# Machine_interlock_controller.net
KiCad netlist of a schematic drawn in Altium Designer
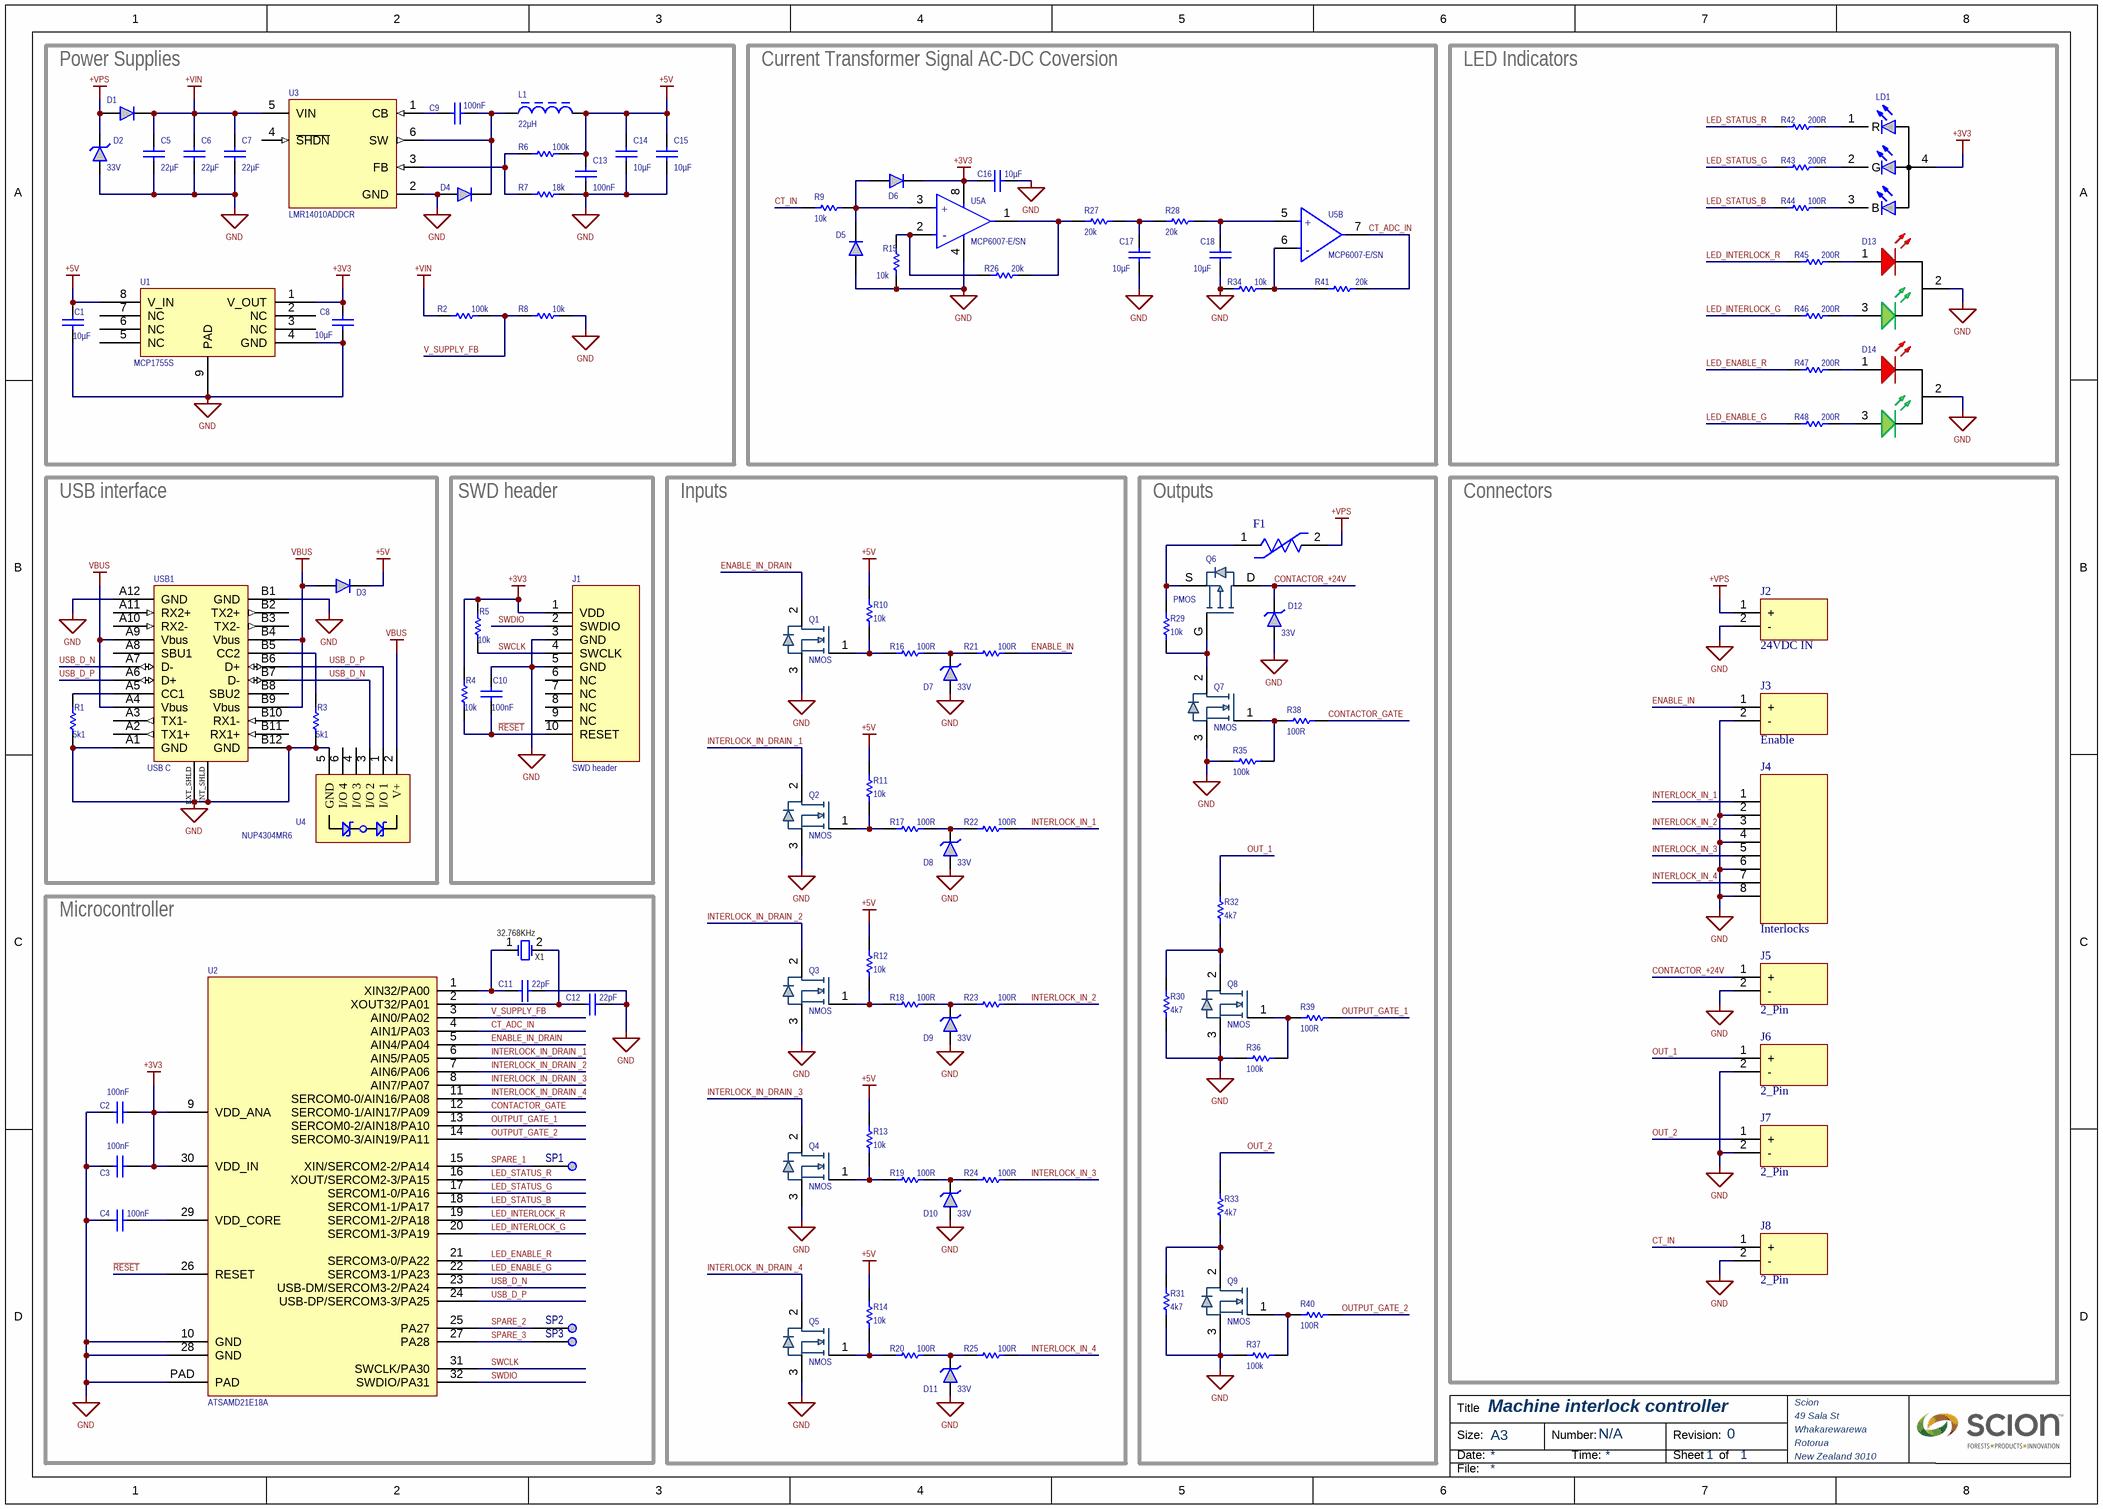
[diagram p0: Machine interlock controller.SchDoc]

(export (version "E")
  (design (tool "Eeschema 10.0.6"))
  (components
    (comp (ref "C1")
      (value "10µF")
      (footprint "0603_CAP")
      (description "SMD Capacitor")
      (fields (field (name "Comment") "Capacitor"))
      (libsource (lib "Scion Research") (part "CMP-019-00005-2"))
    )
    (comp (ref "C2")
      (value "100nF")
      (footprint "0603_CAP")
      (description "SMD Capacitor")
      (fields (field (name "Comment") "Capacitor"))
      (libsource (lib "Scion Research") (part "CMP-019-00005-2"))
    )
    (comp (ref "C3")
      (value "100nF")
      (footprint "0603_CAP")
      (description "SMD Capacitor")
      (fields (field (name "Comment") "Capacitor"))
      (libsource (lib "Scion Research") (part "CMP-019-00005-2"))
    )
    (comp (ref "C4")
      (value "100nF")
      (footprint "0603_CAP")
      (description "SMD Capacitor")
      (fields (field (name "Comment") "Capacitor"))
      (libsource (lib "Scion Research") (part "CMP-019-00005-2"))
    )
    (comp (ref "C5")
      (value "22µF")
      (footprint "0805_CAP")
      (description "SMD Capacitor")
      (fields (field (name "Comment") "Capacitor"))
      (libsource (lib "Scion Research") (part "CMP-019-00005-2"))
    )
    (comp (ref "C6")
      (value "22µF")
      (footprint "0805_CAP")
      (description "SMD Capacitor")
      (fields (field (name "Comment") "Capacitor"))
      (libsource (lib "Scion Research") (part "CMP-019-00005-2"))
    )
    (comp (ref "C7")
      (value "22µF")
      (footprint "0805_CAP")
      (description "SMD Capacitor")
      (fields (field (name "Comment") "Capacitor"))
      (libsource (lib "Scion Research") (part "CMP-019-00005-2"))
    )
    (comp (ref "C8")
      (value "10µF")
      (footprint "0603_CAP")
      (description "SMD Capacitor")
      (fields (field (name "Comment") "Capacitor"))
      (libsource (lib "Scion Research") (part "CMP-019-00005-2"))
    )
    (comp (ref "C9")
      (value "100nF")
      (footprint "0603_CAP")
      (description "SMD Capacitor")
      (fields (field (name "Comment") "Capacitor"))
      (libsource (lib "Scion Research") (part "CMP-019-00005-2"))
    )
    (comp (ref "C10")
      (value "100nF")
      (footprint "0603_CAP")
      (description "SMD Capacitor")
      (fields (field (name "Comment") "Capacitor"))
      (libsource (lib "Scion Research") (part "CMP-019-00005-2"))
    )
    (comp (ref "C11")
      (value "22pF")
      (footprint "0603_CAP")
      (description "SMD Capacitor")
      (fields (field (name "Comment") "Capacitor"))
      (libsource (lib "Scion Research") (part "CMP-019-00005-2"))
    )
    (comp (ref "C12")
      (value "22pF")
      (footprint "0603_CAP")
      (description "SMD Capacitor")
      (fields (field (name "Comment") "Capacitor"))
      (libsource (lib "Scion Research") (part "CMP-019-00005-2"))
    )
    (comp (ref "C13")
      (value "100nF")
      (footprint "0603_CAP")
      (description "SMD Capacitor")
      (fields (field (name "Comment") "Capacitor"))
      (libsource (lib "Scion Research") (part "CMP-019-00005-2"))
    )
    (comp (ref "C14")
      (value "10µF")
      (footprint "0603_CAP")
      (description "SMD Capacitor")
      (fields (field (name "Comment") "Capacitor"))
      (libsource (lib "Scion Research") (part "CMP-019-00005-2"))
    )
    (comp (ref "C15")
      (value "10µF")
      (footprint "0603_CAP")
      (description "SMD Capacitor")
      (fields (field (name "Comment") "Capacitor"))
      (libsource (lib "Scion Research") (part "CMP-019-00005-2"))
    )
    (comp (ref "C16")
      (value "10µF")
      (footprint "0603_CAP")
      (description "SMD Capacitor")
      (fields (field (name "Comment") "Capacitor"))
      (libsource (lib "Scion Research") (part "CMP-019-00005-2"))
    )
    (comp (ref "C17")
      (value "10µF")
      (footprint "0603_CAP")
      (description "SMD Capacitor")
      (fields (field (name "Comment") "Capacitor"))
      (libsource (lib "Scion Research") (part "CMP-019-00005-2"))
    )
    (comp (ref "C18")
      (value "10µF")
      (footprint "0603_CAP")
      (description "SMD Capacitor")
      (fields (field (name "Comment") "Capacitor"))
      (libsource (lib "Scion Research") (part "CMP-019-00005-2"))
    )
    (comp (ref "D1")
      (value "Diode")
      (footprint "SOD-123")
      (description "SMD Diode")
      (libsource (lib "Scion Research") (part "Diode"))
    )
    (comp (ref "D2")
      (value "Transil")
      (footprint "SMBJ")
      (description "Transient Voltage Suppressor")
      (fields (field (name "RATED VOLTAGE") "33V"))
      (libsource (lib "Scion Research") (part "CMP-004-0042-1"))
    )
    (comp (ref "D3")
      (value "Diode")
      (footprint "SOD-123")
      (description "SMD Diode")
      (libsource (lib "Scion Research") (part "Diode"))
    )
    (comp (ref "D4")
      (value "Diode")
      (footprint "SOD-123")
      (description "SMD Diode")
      (libsource (lib "Scion Research") (part "Diode"))
    )
    (comp (ref "D5")
      (value "Diode")
      (footprint "SOD-523")
      (description "SMD Diode")
      (libsource (lib "Scion Research") (part "Diode"))
    )
    (comp (ref "D6")
      (value "Diode")
      (footprint "SOD-523")
      (description "SMD Diode")
      (libsource (lib "Scion Research") (part "Diode"))
    )
    (comp (ref "D7")
      (value "Transil")
      (footprint "SMBJ")
      (description "Transient Voltage Suppressor")
      (fields (field (name "RATED VOLTAGE") "33V"))
      (libsource (lib "Scion Research") (part "CMP-004-0042-1"))
    )
    (comp (ref "D8")
      (value "Transil")
      (footprint "SMBJ")
      (description "Transient Voltage Suppressor")
      (fields (field (name "RATED VOLTAGE") "33V"))
      (libsource (lib "Scion Research") (part "CMP-004-0042-1"))
    )
    (comp (ref "D9")
      (value "Transil")
      (footprint "SMBJ")
      (description "Transient Voltage Suppressor")
      (fields (field (name "RATED VOLTAGE") "33V"))
      (libsource (lib "Scion Research") (part "CMP-004-0042-1"))
    )
    (comp (ref "D10")
      (value "Transil")
      (footprint "SMBJ")
      (description "Transient Voltage Suppressor")
      (fields (field (name "RATED VOLTAGE") "33V"))
      (libsource (lib "Scion Research") (part "CMP-004-0042-1"))
    )
    (comp (ref "D11")
      (value "Transil")
      (footprint "SMBJ")
      (description "Transient Voltage Suppressor")
      (fields (field (name "RATED VOLTAGE") "33V"))
      (libsource (lib "Scion Research") (part "CMP-004-0042-1"))
    )
    (comp (ref "D12")
      (value "Transil")
      (footprint "SMBJ")
      (description "Transient Voltage Suppressor")
      (fields (field (name "RATED VOLTAGE") "33V"))
      (libsource (lib "Scion Research") (part "CMP-004-0042-1"))
    )
    (comp (ref "D13")
      (value "LED 3mm Bi-colour")
      (footprint "LED 3mm Bi-colour-Footprint-1")
      (description "Lite-on LTL1BEKVJNN")
      (libsource (lib "Scion Research") (part "CMP-00043-1"))
    )
    (comp (ref "D14")
      (value "LED 3mm Bi-colour")
      (footprint "LED 3mm Bi-colour-Footprint-1")
      (description "Lite-on LTL1BEKVJNN")
      (libsource (lib "Scion Research") (part "CMP-00043-1"))
    )
    (comp (ref "F1")
      (value "0ZCF0100AF2A")
      (footprint "FP-0ZCF0100AF2A-MFG")
      (description "PTC Resettable Fuse 100A 0.5s 60VDC 0.09 Ohm 2-Pin 2920 T/R")
      (libsource (lib "Scion Research") (part "CMP-00051-1"))
    )
    (comp (ref "J1")
      (value "SWD header")
      (footprint "DIP10_1.27_M_SMD")
      (description "10 Pin Connector")
      (libsource (lib "Scion Research") (part "CMP-002-00071-2"))
    )
    (comp (ref "J2")
      (value "24VDC IN")
      (footprint "2P 3.81mm Header Plugable")
      (description "2 Pin Connector")
      (libsource (lib "Scion Research") (part "CMP-002-00074-8"))
    )
    (comp (ref "J3")
      (value "Enable")
      (footprint "2P 3.81mm Header Plugable")
      (description "2 Pin Connector")
      (libsource (lib "Scion Research") (part "CMP-002-00074-8"))
    )
    (comp (ref "J4")
      (value "Interlocks")
      (footprint "8P 3.81mm Header Plugable")
      (description "8 Pin Connector")
      (libsource (lib "Scion Research") (part "CMP-002-00084-5"))
    )
    (comp (ref "J5")
      (value "2_Pin")
      (footprint "2P 3.81mm Header Plugable")
      (description "2 Pin Connector")
      (libsource (lib "Scion Research") (part "CMP-002-00074-8"))
    )
    (comp (ref "J6")
      (value "2_Pin")
      (footprint "2P 3.81mm Header Plugable")
      (description "2 Pin Connector")
      (libsource (lib "Scion Research") (part "CMP-002-00074-8"))
    )
    (comp (ref "J7")
      (value "2_Pin")
      (footprint "2P 3.81mm Header Plugable")
      (description "2 Pin Connector")
      (libsource (lib "Scion Research") (part "CMP-002-00074-8"))
    )
    (comp (ref "J8")
      (value "2_Pin")
      (footprint "2P 3.81mm Header Plugable")
      (description "2 Pin Connector")
      (libsource (lib "Scion Research") (part "CMP-002-00074-8"))
    )
    (comp (ref "L1")
      (value "22µH")
      (footprint "BOUR-SRN8040_V")
      (description "Power Inductor")
      (fields (field (name "Comment") "Inductor"))
      (libsource (lib "Scion Research") (part "Inductor"))
    )
    (comp (ref "LD1")
      (value "LED_RGB_CA")
      (footprint "LED_RGB_CA")
      (description "Common Annode SMD RGB LED")
      (libsource (lib "Scion Research") (part "CMP-007-00037-1"))
    )
    (comp (ref "Q1")
      (value "NMOS")
      (footprint "SOT-23")
      (description "N Channel MOSFET")
      (libsource (lib "Scion Research") (part "CMP-004-0025-1"))
    )
    (comp (ref "Q2")
      (value "NMOS")
      (footprint "SOT-23")
      (description "N Channel MOSFET")
      (libsource (lib "Scion Research") (part "CMP-004-0025-1"))
    )
    (comp (ref "Q3")
      (value "NMOS")
      (footprint "SOT-23")
      (description "N Channel MOSFET")
      (libsource (lib "Scion Research") (part "CMP-004-0025-1"))
    )
    (comp (ref "Q4")
      (value "NMOS")
      (footprint "SOT-23")
      (description "N Channel MOSFET")
      (libsource (lib "Scion Research") (part "CMP-004-0025-1"))
    )
    (comp (ref "Q5")
      (value "NMOS")
      (footprint "SOT-23")
      (description "N Channel MOSFET")
      (libsource (lib "Scion Research") (part "CMP-004-0025-1"))
    )
    (comp (ref "Q6")
      (value "PMOS")
      (footprint "PowerDI 5060-8")
      (description "P Channel MOSFET")
      (libsource (lib "Scion Research") (part "CMP-004-0035-2"))
    )
    (comp (ref "Q7")
      (value "NMOS")
      (footprint "SOT-23")
      (description "N Channel MOSFET")
      (libsource (lib "Scion Research") (part "CMP-004-0025-1"))
    )
    (comp (ref "Q8")
      (value "NMOS")
      (footprint "SOT-23")
      (description "N Channel MOSFET")
      (libsource (lib "Scion Research") (part "CMP-004-0025-1"))
    )
    (comp (ref "Q9")
      (value "NMOS")
      (footprint "SOT-23")
      (description "N Channel MOSFET")
      (libsource (lib "Scion Research") (part "CMP-004-0025-1"))
    )
    (comp (ref "R1")
      (value "Resistor")
      (footprint "0603_RES")
      (description "SMD Resistor")
      (fields (field (name "ALTIUM_VALUE") "5k1"))
      (libsource (lib "Scion Research") (part "CMP-009-00177-2"))
    )
    (comp (ref "R2")
      (value "Resistor")
      (footprint "0603_RES")
      (description "SMD Resistor")
      (fields (field (name "ALTIUM_VALUE") "100k"))
      (libsource (lib "Scion Research") (part "CMP-009-00177-2"))
    )
    (comp (ref "R3")
      (value "Resistor")
      (footprint "0603_RES")
      (description "SMD Resistor")
      (fields (field (name "ALTIUM_VALUE") "5k1"))
      (libsource (lib "Scion Research") (part "CMP-009-00177-2"))
    )
    (comp (ref "R4")
      (value "Resistor")
      (footprint "0603_RES")
      (description "SMD Resistor")
      (fields (field (name "ALTIUM_VALUE") "10k"))
      (libsource (lib "Scion Research") (part "CMP-009-00177-2"))
    )
    (comp (ref "R5")
      (value "Resistor")
      (footprint "0603_RES")
      (description "SMD Resistor")
      (fields (field (name "ALTIUM_VALUE") "10k"))
      (libsource (lib "Scion Research") (part "CMP-009-00177-2"))
    )
    (comp (ref "R6")
      (value "Resistor")
      (footprint "0603_RES")
      (description "SMD Resistor")
      (fields (field (name "ALTIUM_VALUE") "100k"))
      (libsource (lib "Scion Research") (part "CMP-009-00177-2"))
    )
    (comp (ref "R7")
      (value "Resistor")
      (footprint "0603_RES")
      (description "SMD Resistor")
      (fields (field (name "ALTIUM_VALUE") "18k"))
      (libsource (lib "Scion Research") (part "CMP-009-00177-2"))
    )
    (comp (ref "R8")
      (value "Resistor")
      (footprint "0603_RES")
      (description "SMD Resistor")
      (fields (field (name "ALTIUM_VALUE") "10k"))
      (libsource (lib "Scion Research") (part "CMP-009-00177-2"))
    )
    (comp (ref "R9")
      (value "Resistor")
      (footprint "0603_RES")
      (description "SMD Resistor")
      (fields (field (name "ALTIUM_VALUE") "10k"))
      (libsource (lib "Scion Research") (part "CMP-009-00177-2"))
    )
    (comp (ref "R10")
      (value "Resistor")
      (footprint "0603_RES")
      (description "SMD Resistor")
      (fields (field (name "ALTIUM_VALUE") "10k"))
      (libsource (lib "Scion Research") (part "CMP-009-00177-2"))
    )
    (comp (ref "R11")
      (value "Resistor")
      (footprint "0603_RES")
      (description "SMD Resistor")
      (fields (field (name "ALTIUM_VALUE") "10k"))
      (libsource (lib "Scion Research") (part "CMP-009-00177-2"))
    )
    (comp (ref "R12")
      (value "Resistor")
      (footprint "0603_RES")
      (description "SMD Resistor")
      (fields (field (name "ALTIUM_VALUE") "10k"))
      (libsource (lib "Scion Research") (part "CMP-009-00177-2"))
    )
    (comp (ref "R13")
      (value "Resistor")
      (footprint "0603_RES")
      (description "SMD Resistor")
      (fields (field (name "ALTIUM_VALUE") "10k"))
      (libsource (lib "Scion Research") (part "CMP-009-00177-2"))
    )
    (comp (ref "R14")
      (value "Resistor")
      (footprint "0603_RES")
      (description "SMD Resistor")
      (fields (field (name "ALTIUM_VALUE") "10k"))
      (libsource (lib "Scion Research") (part "CMP-009-00177-2"))
    )
    (comp (ref "R15")
      (value "Resistor")
      (footprint "0603_RES")
      (description "SMD Resistor")
      (fields (field (name "ALTIUM_VALUE") "10k"))
      (libsource (lib "Scion Research") (part "CMP-009-00177-2"))
    )
    (comp (ref "R16")
      (value "Resistor")
      (footprint "0603_RES")
      (description "SMD Resistor")
      (fields (field (name "ALTIUM_VALUE") "100R"))
      (libsource (lib "Scion Research") (part "CMP-009-00177-2"))
    )
    (comp (ref "R17")
      (value "Resistor")
      (footprint "0603_RES")
      (description "SMD Resistor")
      (fields (field (name "ALTIUM_VALUE") "100R"))
      (libsource (lib "Scion Research") (part "CMP-009-00177-2"))
    )
    (comp (ref "R18")
      (value "Resistor")
      (footprint "0603_RES")
      (description "SMD Resistor")
      (fields (field (name "ALTIUM_VALUE") "100R"))
      (libsource (lib "Scion Research") (part "CMP-009-00177-2"))
    )
    (comp (ref "R19")
      (value "Resistor")
      (footprint "0603_RES")
      (description "SMD Resistor")
      (fields (field (name "ALTIUM_VALUE") "100R"))
      (libsource (lib "Scion Research") (part "CMP-009-00177-2"))
    )
    (comp (ref "R20")
      (value "Resistor")
      (footprint "0603_RES")
      (description "SMD Resistor")
      (fields (field (name "ALTIUM_VALUE") "100R"))
      (libsource (lib "Scion Research") (part "CMP-009-00177-2"))
    )
    (comp (ref "R21")
      (value "Resistor")
      (footprint "0603_RES")
      (description "SMD Resistor")
      (fields (field (name "ALTIUM_VALUE") "100R"))
      (libsource (lib "Scion Research") (part "CMP-009-00177-2"))
    )
    (comp (ref "R22")
      (value "Resistor")
      (footprint "0603_RES")
      (description "SMD Resistor")
      (fields (field (name "ALTIUM_VALUE") "100R"))
      (libsource (lib "Scion Research") (part "CMP-009-00177-2"))
    )
    (comp (ref "R23")
      (value "Resistor")
      (footprint "0603_RES")
      (description "SMD Resistor")
      (fields (field (name "ALTIUM_VALUE") "100R"))
      (libsource (lib "Scion Research") (part "CMP-009-00177-2"))
    )
    (comp (ref "R24")
      (value "Resistor")
      (footprint "0603_RES")
      (description "SMD Resistor")
      (fields (field (name "ALTIUM_VALUE") "100R"))
      (libsource (lib "Scion Research") (part "CMP-009-00177-2"))
    )
    (comp (ref "R25")
      (value "Resistor")
      (footprint "0603_RES")
      (description "SMD Resistor")
      (fields (field (name "ALTIUM_VALUE") "100R"))
      (libsource (lib "Scion Research") (part "CMP-009-00177-2"))
    )
    (comp (ref "R26")
      (value "Resistor")
      (footprint "0603_RES")
      (description "SMD Resistor")
      (fields (field (name "ALTIUM_VALUE") "20k"))
      (libsource (lib "Scion Research") (part "CMP-009-00177-2"))
    )
    (comp (ref "R27")
      (value "Resistor")
      (footprint "0603_RES")
      (description "SMD Resistor")
      (fields (field (name "ALTIUM_VALUE") "20k"))
      (libsource (lib "Scion Research") (part "CMP-009-00177-2"))
    )
    (comp (ref "R28")
      (value "Resistor")
      (footprint "0603_RES")
      (description "SMD Resistor")
      (fields (field (name "ALTIUM_VALUE") "20k"))
      (libsource (lib "Scion Research") (part "CMP-009-00177-2"))
    )
    (comp (ref "R29")
      (value "Resistor")
      (footprint "0603_RES")
      (description "SMD Resistor")
      (fields (field (name "ALTIUM_VALUE") "10k"))
      (libsource (lib "Scion Research") (part "CMP-009-00177-2"))
    )
    (comp (ref "R30")
      (value "Resistor")
      (footprint "0603_RES")
      (description "SMD Resistor")
      (fields (field (name "ALTIUM_VALUE") "4k7"))
      (libsource (lib "Scion Research") (part "CMP-009-00177-2"))
    )
    (comp (ref "R31")
      (value "Resistor")
      (footprint "0603_RES")
      (description "SMD Resistor")
      (fields (field (name "ALTIUM_VALUE") "4k7"))
      (libsource (lib "Scion Research") (part "CMP-009-00177-2"))
    )
    (comp (ref "R32")
      (value "Resistor")
      (footprint "0603_RES")
      (description "SMD Resistor")
      (fields (field (name "ALTIUM_VALUE") "4k7"))
      (libsource (lib "Scion Research") (part "CMP-009-00177-2"))
    )
    (comp (ref "R33")
      (value "Resistor")
      (footprint "0603_RES")
      (description "SMD Resistor")
      (fields (field (name "ALTIUM_VALUE") "4k7"))
      (libsource (lib "Scion Research") (part "CMP-009-00177-2"))
    )
    (comp (ref "R34")
      (value "Resistor")
      (footprint "0603_RES")
      (description "SMD Resistor")
      (fields (field (name "ALTIUM_VALUE") "10k"))
      (libsource (lib "Scion Research") (part "CMP-009-00177-2"))
    )
    (comp (ref "R35")
      (value "Resistor")
      (footprint "0603_RES")
      (description "SMD Resistor")
      (fields (field (name "ALTIUM_VALUE") "100k"))
      (libsource (lib "Scion Research") (part "CMP-009-00177-2"))
    )
    (comp (ref "R36")
      (value "Resistor")
      (footprint "0603_RES")
      (description "SMD Resistor")
      (fields (field (name "ALTIUM_VALUE") "100k"))
      (libsource (lib "Scion Research") (part "CMP-009-00177-2"))
    )
    (comp (ref "R37")
      (value "Resistor")
      (footprint "0603_RES")
      (description "SMD Resistor")
      (fields (field (name "ALTIUM_VALUE") "100k"))
      (libsource (lib "Scion Research") (part "CMP-009-00177-2"))
    )
    (comp (ref "R38")
      (value "Resistor")
      (footprint "0603_RES")
      (description "SMD Resistor")
      (fields (field (name "ALTIUM_VALUE") "100R"))
      (libsource (lib "Scion Research") (part "CMP-009-00177-2"))
    )
    (comp (ref "R39")
      (value "Resistor")
      (footprint "0603_RES")
      (description "SMD Resistor")
      (fields (field (name "ALTIUM_VALUE") "100R"))
      (libsource (lib "Scion Research") (part "CMP-009-00177-2"))
    )
    (comp (ref "R40")
      (value "Resistor")
      (footprint "0603_RES")
      (description "SMD Resistor")
      (fields (field (name "ALTIUM_VALUE") "100R"))
      (libsource (lib "Scion Research") (part "CMP-009-00177-2"))
    )
    (comp (ref "R41")
      (value "Resistor")
      (footprint "0603_RES")
      (description "SMD Resistor")
      (fields (field (name "ALTIUM_VALUE") "20k"))
      (libsource (lib "Scion Research") (part "CMP-009-00177-2"))
    )
    (comp (ref "R42")
      (value "Resistor")
      (footprint "0603_RES")
      (description "SMD Resistor")
      (fields (field (name "ALTIUM_VALUE") "200R"))
      (libsource (lib "Scion Research") (part "CMP-009-00177-2"))
    )
    (comp (ref "R43")
      (value "Resistor")
      (footprint "0603_RES")
      (description "SMD Resistor")
      (fields (field (name "ALTIUM_VALUE") "200R"))
      (libsource (lib "Scion Research") (part "CMP-009-00177-2"))
    )
    (comp (ref "R44")
      (value "Resistor")
      (footprint "0603_RES")
      (description "SMD Resistor")
      (fields (field (name "ALTIUM_VALUE") "100R"))
      (libsource (lib "Scion Research") (part "CMP-009-00177-2"))
    )
    (comp (ref "R45")
      (value "Resistor")
      (footprint "0603_RES")
      (description "SMD Resistor")
      (fields (field (name "ALTIUM_VALUE") "200R"))
      (libsource (lib "Scion Research") (part "CMP-009-00177-2"))
    )
    (comp (ref "R46")
      (value "Resistor")
      (footprint "0603_RES")
      (description "SMD Resistor")
      (fields (field (name "ALTIUM_VALUE") "200R"))
      (libsource (lib "Scion Research") (part "CMP-009-00177-2"))
    )
    (comp (ref "R47")
      (value "Resistor")
      (footprint "0603_RES")
      (description "SMD Resistor")
      (fields (field (name "ALTIUM_VALUE") "200R"))
      (libsource (lib "Scion Research") (part "CMP-009-00177-2"))
    )
    (comp (ref "R48")
      (value "Resistor")
      (footprint "0603_RES")
      (description "SMD Resistor")
      (fields (field (name "ALTIUM_VALUE") "200R"))
      (libsource (lib "Scion Research") (part "CMP-009-00177-2"))
    )
    (comp (ref "SP1")
      (value "CMP-00044-2")
      (footprint "Prog Pad 1.5 x 2.5mm")
      (description "Programmer pogo-pin interface pad (or test pad)")
      (libsource (lib "Scion Research") (part "CMP-00044-2"))
    )
    (comp (ref "SP2")
      (value "CMP-00044-2")
      (footprint "Prog Pad 1.5 x 2.5mm")
      (description "Programmer pogo-pin interface pad (or test pad)")
      (libsource (lib "Scion Research") (part "CMP-00044-2"))
    )
    (comp (ref "SP3")
      (value "CMP-00044-2")
      (footprint "Prog Pad 1.5 x 2.5mm")
      (description "Programmer pogo-pin interface pad (or test pad)")
      (libsource (lib "Scion Research") (part "CMP-00044-2"))
    )
    (comp (ref "U1")
      (value "MCP1755S")
      (footprint "8P 2x3 DFN")
      (description "LDO Linear Voltage Regulator")
      (libsource (lib "Scion Research") (part "CMP-004-0021-1"))
    )
    (comp (ref "U2")
      (value "ATSAMD21E18A")
      (footprint "32P QFN")
      (libsource (lib "Scion Research") (part "CMP-00013-1"))
    )
    (comp (ref "U3")
      (value "LMR14010ADDCR")
      (footprint "FP-DDC0006A-IPC_A")
      (description "7-40VDC-DC buck converter")
      (libsource (lib "Scion Research") (part "LMR14010"))
    )
    (comp (ref "U4")
      (value "NUP4304MR6")
      (footprint "TSOP-6")
      (description "ESD Protection Doide Array")
      (libsource (lib "Scion Research") (part "CMP-004-0028-1"))
    )
    (comp (ref "U5")
      (value "MCP6007-E/SN")
      (footprint "FP-C04-057-SN-IPC_A")
      (description "IC OPAMP GP 2 CIRCUIT 8SOIC")
      (libsource (lib "Altium Content Vault") (part "4f0eb9cc04af1aa3743a6352a5ae503"))
    )
    (comp (ref "USB1")
      (value "USB C")
      (footprint "GT-USB-7090A")
      (description "Vertical or RA Type C Usb Connector Rohs Compliant: Yes")
      (libsource (lib "Scion Research") (part "CMP-00005-5"))
    )
    (comp (ref "X1")
      (value "32.768KHz")
      (footprint "ABRA-ABS07-2_V")
      (fields (field (name "TOLERANCE") "20ppm") (field (name "MANUFACTURER") "Abracon"))
      (libsource (lib "Scion Research") (part "CMP-003-00022-1"))
    )
  )
  (nets
    (net (code "1") (name "+3V3") (class "Default")
      (node (ref "C16") (pin "1") (pinfunction "1_1") (pintype "passive"))
      (node (ref "C2") (pin "1") (pinfunction "1_1") (pintype "passive"))
      (node (ref "C3") (pin "1") (pinfunction "1_1") (pintype "passive"))
      (node (ref "C8") (pin "1") (pinfunction "1_1") (pintype "passive"))
      (node (ref "D6") (pin "1") (pinfunction "K_1") (pintype "passive"))
      (node (ref "J1") (pin "1") (pinfunction "VDD_1") (pintype "passive"))
      (node (ref "LD1") (pin "4") (pinfunction "A_4") (pintype "power_in"))
      (node (ref "R4") (pin "1") (pinfunction "1_1") (pintype "passive"))
      (node (ref "R5") (pin "1") (pinfunction "1_1") (pintype "passive"))
      (node (ref "U1") (pin "1") (pinfunction "V_OUT_1") (pintype "power_in"))
      (node (ref "U2") (pin "30") (pinfunction "VDD_IN_30") (pintype "passive"))
      (node (ref "U2") (pin "9") (pinfunction "VDD_ANA_9") (pintype "passive"))
      (node (ref "U5") (pin "8") (pinfunction "VDD_8") (pintype "power_in"))
    )
    (net (code "2") (name "+5V") (class "Default")
      (node (ref "C1") (pin "1") (pinfunction "1_1") (pintype "passive"))
      (node (ref "C13") (pin "1") (pinfunction "1_1") (pintype "passive"))
      (node (ref "C14") (pin "1") (pinfunction "1_1") (pintype "passive"))
      (node (ref "C15") (pin "1") (pinfunction "1_1") (pintype "passive"))
      (node (ref "D3") (pin "1") (pinfunction "K_1") (pintype "passive"))
      (node (ref "L1") (pin "2") (pinfunction "2_2") (pintype "passive"))
      (node (ref "R10") (pin "1") (pinfunction "1_1") (pintype "passive"))
      (node (ref "R11") (pin "1") (pinfunction "1_1") (pintype "passive"))
      (node (ref "R12") (pin "1") (pinfunction "1_1") (pintype "passive"))
      (node (ref "R13") (pin "1") (pinfunction "1_1") (pintype "passive"))
      (node (ref "R14") (pin "1") (pinfunction "1_1") (pintype "passive"))
      (node (ref "R6") (pin "2") (pinfunction "2_2") (pintype "passive"))
      (node (ref "U1") (pin "8") (pinfunction "V_IN_8") (pintype "power_in"))
    )
    (net (code "3") (name "+VIN") (class "Default")
      (node (ref "C5") (pin "1") (pinfunction "1_1") (pintype "passive"))
      (node (ref "C6") (pin "1") (pinfunction "1_1") (pintype "passive"))
      (node (ref "C7") (pin "1") (pinfunction "1_1") (pintype "passive"))
      (node (ref "D1") (pin "1") (pinfunction "K_1") (pintype "passive"))
      (node (ref "R2") (pin "1") (pinfunction "1_1") (pintype "passive"))
      (node (ref "U3") (pin "5") (pinfunction "VIN_5") (pintype "power_in"))
    )
    (net (code "4") (name "+VPS") (class "Default")
      (node (ref "D1") (pin "2") (pinfunction "A_2") (pintype "passive"))
      (node (ref "D2") (pin "2") (pinfunction "K_2") (pintype "passive"))
      (node (ref "F1") (pin "2") (pinfunction "2_2") (pintype "passive"))
      (node (ref "J2") (pin "1") (pinfunction "+_1") (pintype "passive"))
    )
    (net (code "5") (name "/CONTACTOR_+24V") (class "Default")
      (node (ref "D12") (pin "2") (pinfunction "K_2") (pintype "passive"))
      (node (ref "J5") (pin "1") (pinfunction "+_1") (pintype "passive"))
      (node (ref "Q6") (pin "D") (pinfunction "D_D") (pintype "passive"))
    )
    (net (code "6") (name "/CONTACTOR_GATE") (class "Default")
      (node (ref "R38") (pin "2") (pinfunction "2_2") (pintype "passive"))
      (node (ref "U2") (pin "12") (pinfunction "SERCOM0-1/AIN17/PA09_12") (pintype "passive"))
    )
    (net (code "7") (name "/CT_ADC_IN") (class "Default")
      (node (ref "R41") (pin "2") (pinfunction "2_2") (pintype "passive"))
      (node (ref "U2") (pin "4") (pinfunction "AIN1/PA03_4") (pintype "passive"))
      (node (ref "U5") (pin "7") (pinfunction "VOUTB_7") (pintype "passive"))
    )
    (net (code "8") (name "/CT_IN") (class "Default")
      (node (ref "J8") (pin "1") (pinfunction "+_1") (pintype "passive"))
      (node (ref "R9") (pin "2") (pinfunction "2_2") (pintype "passive"))
    )
    (net (code "9") (name "/ENABLE_IN") (class "Default")
      (node (ref "J3") (pin "1") (pinfunction "+_1") (pintype "passive"))
      (node (ref "R21") (pin "2") (pinfunction "2_2") (pintype "passive"))
    )
    (net (code "10") (name "/ENABLE_IN_DRAIN") (class "Default")
      (node (ref "Q1") (pin "2") (pinfunction "D_2") (pintype "passive"))
      (node (ref "U2") (pin "5") (pinfunction "AIN4/PA04_5") (pintype "passive"))
    )
    (net (code "11") (name "/INTERLOCK_IN_1") (class "Default")
      (node (ref "J4") (pin "1") (pinfunction "1_1") (pintype "passive"))
      (node (ref "R22") (pin "2") (pinfunction "2_2") (pintype "passive"))
    )
    (net (code "12") (name "/INTERLOCK_IN_2") (class "Default")
      (node (ref "J4") (pin "3") (pinfunction "3_3") (pintype "passive"))
      (node (ref "R23") (pin "2") (pinfunction "2_2") (pintype "passive"))
    )
    (net (code "13") (name "/INTERLOCK_IN_3") (class "Default")
      (node (ref "J4") (pin "5") (pinfunction "5_5") (pintype "passive"))
      (node (ref "R24") (pin "2") (pinfunction "2_2") (pintype "passive"))
    )
    (net (code "14") (name "/INTERLOCK_IN_4") (class "Default")
      (node (ref "J4") (pin "7") (pinfunction "7_7") (pintype "passive"))
      (node (ref "R25") (pin "2") (pinfunction "2_2") (pintype "passive"))
    )
    (net (code "15") (name "/INTERLOCK_IN_DRAIN _1") (class "Default")
      (node (ref "Q2") (pin "2") (pinfunction "D_2") (pintype "passive"))
      (node (ref "U2") (pin "6") (pinfunction "AIN5/PA05_6") (pintype "passive"))
    )
    (net (code "16") (name "/INTERLOCK_IN_DRAIN _2") (class "Default")
      (node (ref "Q3") (pin "2") (pinfunction "D_2") (pintype "passive"))
      (node (ref "U2") (pin "7") (pinfunction "AIN6/PA06_7") (pintype "passive"))
    )
    (net (code "17") (name "/INTERLOCK_IN_DRAIN _3") (class "Default")
      (node (ref "Q4") (pin "2") (pinfunction "D_2") (pintype "passive"))
      (node (ref "U2") (pin "8") (pinfunction "AIN7/PA07_8") (pintype "passive"))
    )
    (net (code "18") (name "/INTERLOCK_IN_DRAIN _4") (class "Default")
      (node (ref "Q5") (pin "2") (pinfunction "D_2") (pintype "passive"))
      (node (ref "U2") (pin "11") (pinfunction "SERCOM0-0/AIN16/PA08_11") (pintype "passive"))
    )
    (net (code "19") (name "/LED_ENABLE_G") (class "Default")
      (node (ref "R48") (pin "1") (pinfunction "1_1") (pintype "passive"))
      (node (ref "U2") (pin "22") (pinfunction "SERCOM3-1/PA23_22") (pintype "passive"))
    )
    (net (code "20") (name "/LED_ENABLE_R") (class "Default")
      (node (ref "R47") (pin "1") (pinfunction "1_1") (pintype "passive"))
      (node (ref "U2") (pin "21") (pinfunction "SERCOM3-0/PA22_21") (pintype "passive"))
    )
    (net (code "21") (name "/LED_INTERLOCK_G") (class "Default")
      (node (ref "R46") (pin "1") (pinfunction "1_1") (pintype "passive"))
      (node (ref "U2") (pin "20") (pinfunction "SERCOM1-3/PA19_20") (pintype "passive"))
    )
    (net (code "22") (name "/LED_INTERLOCK_R") (class "Default")
      (node (ref "R45") (pin "1") (pinfunction "1_1") (pintype "passive"))
      (node (ref "U2") (pin "19") (pinfunction "SERCOM1-2/PA18_19") (pintype "passive"))
    )
    (net (code "23") (name "/LED_STATUS_B") (class "Default")
      (node (ref "R44") (pin "1") (pinfunction "1_1") (pintype "passive"))
      (node (ref "U2") (pin "18") (pinfunction "SERCOM1-1/PA17_18") (pintype "passive"))
    )
    (net (code "24") (name "/LED_STATUS_G") (class "Default")
      (node (ref "R43") (pin "1") (pinfunction "1_1") (pintype "passive"))
      (node (ref "U2") (pin "17") (pinfunction "SERCOM1-0/PA16_17") (pintype "passive"))
    )
    (net (code "25") (name "/LED_STATUS_R") (class "Default")
      (node (ref "R42") (pin "1") (pinfunction "1_1") (pintype "passive"))
      (node (ref "U2") (pin "16") (pinfunction "XOUT/SERCOM2-3/PA15_16") (pintype "passive"))
    )
    (net (code "26") (name "/OUTPUT_GATE_1") (class "Default")
      (node (ref "R39") (pin "2") (pinfunction "2_2") (pintype "passive"))
      (node (ref "U2") (pin "13") (pinfunction "SERCOM0-2/AIN18/PA10_13") (pintype "passive"))
    )
    (net (code "27") (name "/OUTPUT_GATE_2") (class "Default")
      (node (ref "R40") (pin "2") (pinfunction "2_2") (pintype "passive"))
      (node (ref "U2") (pin "14") (pinfunction "SERCOM0-3/AIN19/PA11_14") (pintype "passive"))
    )
    (net (code "28") (name "/OUT_1") (class "Default")
      (node (ref "J6") (pin "1") (pinfunction "+_1") (pintype "passive"))
      (node (ref "R32") (pin "1") (pinfunction "1_1") (pintype "passive"))
    )
    (net (code "29") (name "/OUT_2") (class "Default")
      (node (ref "J7") (pin "1") (pinfunction "+_1") (pintype "passive"))
      (node (ref "R33") (pin "1") (pinfunction "1_1") (pintype "passive"))
    )
    (net (code "30") (name "/SPARE_1") (class "Default")
      (node (ref "SP1") (pin "1") (pinfunction "1_1") (pintype "passive"))
      (node (ref "U2") (pin "15") (pinfunction "XIN/SERCOM2-2/PA14_15") (pintype "passive"))
    )
    (net (code "31") (name "/SPARE_2") (class "Default")
      (node (ref "SP2") (pin "1") (pinfunction "1_1") (pintype "passive"))
      (node (ref "U2") (pin "25") (pinfunction "PA27_25") (pintype "passive"))
    )
    (net (code "32") (name "/SPARE_3") (class "Default")
      (node (ref "SP3") (pin "1") (pinfunction "1_1") (pintype "passive"))
      (node (ref "U2") (pin "27") (pinfunction "PA28_27") (pintype "passive"))
    )
    (net (code "33") (name "/SWCLK") (class "Default")
      (node (ref "J1") (pin "4") (pinfunction "SWCLK_4") (pintype "passive"))
      (node (ref "R5") (pin "2") (pinfunction "2_2") (pintype "passive"))
      (node (ref "U2") (pin "31") (pinfunction "SWCLK/PA30_31") (pintype "passive"))
    )
    (net (code "34") (name "/SWDIO") (class "Default")
      (node (ref "J1") (pin "2") (pinfunction "SWDIO_2") (pintype "passive"))
      (node (ref "U2") (pin "32") (pinfunction "SWDIO/PA31_32") (pintype "passive"))
    )
    (net (code "35") (name "/USB_D_N") (class "Default")
      (node (ref "U2") (pin "23") (pinfunction "USB-DM/SERCOM3-2/PA24_23") (pintype "passive"))
      (node (ref "U4") (pin "3") (pinfunction "I/O_2_3") (pintype "power_in"))
      (node (ref "USB1") (pin "A7") (pinfunction "D-_A7") (pintype "bidirectional"))
      (node (ref "USB1") (pin "B7") (pinfunction "D-_B7") (pintype "bidirectional"))
    )
    (net (code "36") (name "/USB_D_P") (class "Default")
      (node (ref "U2") (pin "24") (pinfunction "USB-DP/SERCOM3-3/PA25_24") (pintype "passive"))
      (node (ref "U4") (pin "1") (pinfunction "I/O_1_1") (pintype "power_in"))
      (node (ref "USB1") (pin "A6") (pinfunction "D+_A6") (pintype "bidirectional"))
      (node (ref "USB1") (pin "B6") (pinfunction "D+_B6") (pintype "bidirectional"))
    )
    (net (code "37") (name "/V_SUPPLY_FB") (class "Default")
      (node (ref "R2") (pin "2") (pinfunction "2_2") (pintype "passive"))
      (node (ref "R8") (pin "1") (pinfunction "1_1") (pintype "passive"))
      (node (ref "U2") (pin "3") (pinfunction "AIN0/PA02_3") (pintype "passive"))
    )
    (net (code "38") (name "/~{RESET}") (class "Default")
      (node (ref "C10") (pin "2") (pinfunction "2_2") (pintype "passive"))
      (node (ref "J1") (pin "10") (pinfunction "RESET_10") (pintype "passive"))
      (node (ref "R4") (pin "2") (pinfunction "2_2") (pintype "passive"))
      (node (ref "U2") (pin "26") (pinfunction "RESET_26") (pintype "passive"))
    )
    (net (code "39") (name "GND") (class "Default")
      (node (ref "C1") (pin "2") (pinfunction "2_2") (pintype "passive"))
      (node (ref "C10") (pin "1") (pinfunction "1_1") (pintype "passive"))
      (node (ref "C11") (pin "1") (pinfunction "1_1") (pintype "passive"))
      (node (ref "C12") (pin "2") (pinfunction "2_2") (pintype "passive"))
      (node (ref "C13") (pin "2") (pinfunction "2_2") (pintype "passive"))
      (node (ref "C14") (pin "2") (pinfunction "2_2") (pintype "passive"))
      (node (ref "C15") (pin "2") (pinfunction "2_2") (pintype "passive"))
      (node (ref "C16") (pin "2") (pinfunction "2_2") (pintype "passive"))
      (node (ref "C17") (pin "2") (pinfunction "2_2") (pintype "passive"))
      (node (ref "C18") (pin "2") (pinfunction "2_2") (pintype "passive"))
      (node (ref "C2") (pin "2") (pinfunction "2_2") (pintype "passive"))
      (node (ref "C3") (pin "2") (pinfunction "2_2") (pintype "passive"))
      (node (ref "C4") (pin "2") (pinfunction "2_2") (pintype "passive"))
      (node (ref "C5") (pin "2") (pinfunction "2_2") (pintype "passive"))
      (node (ref "C6") (pin "2") (pinfunction "2_2") (pintype "passive"))
      (node (ref "C7") (pin "2") (pinfunction "2_2") (pintype "passive"))
      (node (ref "C8") (pin "2") (pinfunction "2_2") (pintype "passive"))
      (node (ref "D10") (pin "1") (pinfunction "A_1") (pintype "passive"))
      (node (ref "D11") (pin "1") (pinfunction "A_1") (pintype "passive"))
      (node (ref "D12") (pin "1") (pinfunction "A_1") (pintype "passive"))
      (node (ref "D13") (pin "2") (pinfunction "Cathode_2") (pintype "passive"))
      (node (ref "D14") (pin "2") (pinfunction "Cathode_2") (pintype "passive"))
      (node (ref "D2") (pin "1") (pinfunction "A_1") (pintype "passive"))
      (node (ref "D4") (pin "2") (pinfunction "A_2") (pintype "passive"))
      (node (ref "D5") (pin "2") (pinfunction "A_2") (pintype "passive"))
      (node (ref "D7") (pin "1") (pinfunction "A_1") (pintype "passive"))
      (node (ref "D8") (pin "1") (pinfunction "A_1") (pintype "passive"))
      (node (ref "D9") (pin "1") (pinfunction "A_1") (pintype "passive"))
      (node (ref "J1") (pin "3") (pinfunction "GND_3") (pintype "passive"))
      (node (ref "J1") (pin "5") (pinfunction "GND_5") (pintype "passive"))
      (node (ref "J2") (pin "2") (pinfunction "-_2") (pintype "passive"))
      (node (ref "J3") (pin "2") (pinfunction "-_2") (pintype "passive"))
      (node (ref "J4") (pin "2") (pinfunction "2_2") (pintype "passive"))
      (node (ref "J4") (pin "4") (pinfunction "4_4") (pintype "passive"))
      (node (ref "J4") (pin "6") (pinfunction "6_6") (pintype "passive"))
      (node (ref "J4") (pin "8") (pinfunction "8_8") (pintype "passive"))
      (node (ref "J5") (pin "2") (pinfunction "-_2") (pintype "passive"))
      (node (ref "J6") (pin "2") (pinfunction "-_2") (pintype "passive"))
      (node (ref "J7") (pin "2") (pinfunction "-_2") (pintype "passive"))
      (node (ref "J8") (pin "2") (pinfunction "-_2") (pintype "passive"))
      (node (ref "Q1") (pin "3") (pinfunction "S_3") (pintype "passive"))
      (node (ref "Q2") (pin "3") (pinfunction "S_3") (pintype "passive"))
      (node (ref "Q3") (pin "3") (pinfunction "S_3") (pintype "passive"))
      (node (ref "Q4") (pin "3") (pinfunction "S_3") (pintype "passive"))
      (node (ref "Q5") (pin "3") (pinfunction "S_3") (pintype "passive"))
      (node (ref "Q7") (pin "3") (pinfunction "S_3") (pintype "passive"))
      (node (ref "Q8") (pin "3") (pinfunction "S_3") (pintype "passive"))
      (node (ref "Q9") (pin "3") (pinfunction "S_3") (pintype "passive"))
      (node (ref "R1") (pin "2") (pinfunction "2_2") (pintype "passive"))
      (node (ref "R15") (pin "2") (pinfunction "2_2") (pintype "passive"))
      (node (ref "R3") (pin "2") (pinfunction "2_2") (pintype "passive"))
      (node (ref "R30") (pin "2") (pinfunction "2_2") (pintype "passive"))
      (node (ref "R31") (pin "2") (pinfunction "2_2") (pintype "passive"))
      (node (ref "R34") (pin "1") (pinfunction "1_1") (pintype "passive"))
      (node (ref "R35") (pin "1") (pinfunction "1_1") (pintype "passive"))
      (node (ref "R36") (pin "1") (pinfunction "1_1") (pintype "passive"))
      (node (ref "R37") (pin "1") (pinfunction "1_1") (pintype "passive"))
      (node (ref "R7") (pin "2") (pinfunction "2_2") (pintype "passive"))
      (node (ref "R8") (pin "2") (pinfunction "2_2") (pintype "passive"))
      (node (ref "U1") (pin "4") (pinfunction "GND_4") (pintype "power_in"))
      (node (ref "U1") (pin "9") (pinfunction "PAD_9") (pintype "power_in"))
      (node (ref "U2") (pin "10") (pinfunction "GND_10") (pintype "passive"))
      (node (ref "U2") (pin "28") (pinfunction "GND_28") (pintype "passive"))
      (node (ref "U2") (pin "PAD") (pinfunction "PAD_PAD") (pintype "passive"))
      (node (ref "U3") (pin "2") (pinfunction "GND_2") (pintype "power_in"))
      (node (ref "U4") (pin "5") (pinfunction "GND_5") (pintype "power_in"))
      (node (ref "U5") (pin "4") (pinfunction "VSS_4") (pintype "power_in"))
      (node (ref "USB1") (pin "A1") (pinfunction "GND_A1") (pintype "power_in"))
      (node (ref "USB1") (pin "A12") (pinfunction "GND_A12") (pintype "power_in"))
      (node (ref "USB1") (pin "B1") (pinfunction "GND_B1") (pintype "power_in"))
      (node (ref "USB1") (pin "B12") (pinfunction "GND_B12") (pintype "power_in"))
      (node (ref "USB1") (pin "EXT_SHLD") (pintype "passive"))
      (node (ref "USB1") (pin "INT_SHLD") (pintype "passive"))
    )
    (net (code "40") (name "Net-(C17-Pad1)") (class "Default")
      (node (ref "C17") (pin "1") (pinfunction "1_1") (pintype "passive"))
      (node (ref "R27") (pin "2") (pinfunction "2_2") (pintype "passive"))
      (node (ref "R28") (pin "1") (pinfunction "1_1") (pintype "passive"))
    )
    (net (code "41") (name "Net-(D4-K)") (class "Default")
      (node (ref "C9") (pin "1") (pinfunction "1_1") (pintype "passive"))
      (node (ref "D4") (pin "1") (pinfunction "K_1") (pintype "passive"))
      (node (ref "L1") (pin "1") (pinfunction "1_1") (pintype "passive"))
      (node (ref "U3") (pin "6") (pinfunction "SW_6") (pintype "output"))
    )
    (net (code "42") (name "Net-(D5-K)") (class "Default")
      (node (ref "D5") (pin "1") (pinfunction "K_1") (pintype "passive"))
      (node (ref "D6") (pin "2") (pinfunction "A_2") (pintype "passive"))
      (node (ref "R9") (pin "1") (pinfunction "1_1") (pintype "passive"))
      (node (ref "U5") (pin "3") (pinfunction "VINA+_3") (pintype "tri_state"))
    )
    (net (code "43") (name "Net-(D7-K)") (class "Default")
      (node (ref "D7") (pin "2") (pinfunction "K_2") (pintype "passive"))
      (node (ref "R16") (pin "2") (pinfunction "2_2") (pintype "passive"))
      (node (ref "R21") (pin "1") (pinfunction "1_1") (pintype "passive"))
    )
    (net (code "44") (name "Net-(D8-K)") (class "Default")
      (node (ref "D8") (pin "2") (pinfunction "K_2") (pintype "passive"))
      (node (ref "R17") (pin "2") (pinfunction "2_2") (pintype "passive"))
      (node (ref "R22") (pin "1") (pinfunction "1_1") (pintype "passive"))
    )
    (net (code "45") (name "Net-(D9-K)") (class "Default")
      (node (ref "D9") (pin "2") (pinfunction "K_2") (pintype "passive"))
      (node (ref "R18") (pin "2") (pinfunction "2_2") (pintype "passive"))
      (node (ref "R23") (pin "1") (pinfunction "1_1") (pintype "passive"))
    )
    (net (code "46") (name "Net-(D10-K)") (class "Default")
      (node (ref "D10") (pin "2") (pinfunction "K_2") (pintype "passive"))
      (node (ref "R19") (pin "2") (pinfunction "2_2") (pintype "passive"))
      (node (ref "R24") (pin "1") (pinfunction "1_1") (pintype "passive"))
    )
    (net (code "47") (name "Net-(D11-K)") (class "Default")
      (node (ref "D11") (pin "2") (pinfunction "K_2") (pintype "passive"))
      (node (ref "R20") (pin "2") (pinfunction "2_2") (pintype "passive"))
      (node (ref "R25") (pin "1") (pinfunction "1_1") (pintype "passive"))
    )
    (net (code "48") (name "Net-(D13-Green_Annode)") (class "Default")
      (node (ref "D13") (pin "3") (pinfunction "Green_Annode_3") (pintype "passive"))
      (node (ref "R46") (pin "2") (pinfunction "2_2") (pintype "passive"))
    )
    (net (code "49") (name "Net-(D13-Red_Annode)") (class "Default")
      (node (ref "D13") (pin "1") (pinfunction "Red_Annode_1") (pintype "passive"))
      (node (ref "R45") (pin "2") (pinfunction "2_2") (pintype "passive"))
    )
    (net (code "50") (name "Net-(D14-Green_Annode)") (class "Default")
      (node (ref "D14") (pin "3") (pinfunction "Green_Annode_3") (pintype "passive"))
      (node (ref "R48") (pin "2") (pinfunction "2_2") (pintype "passive"))
    )
    (net (code "51") (name "Net-(D14-Red_Annode)") (class "Default")
      (node (ref "D14") (pin "1") (pinfunction "Red_Annode_1") (pintype "passive"))
      (node (ref "R47") (pin "2") (pinfunction "2_2") (pintype "passive"))
    )
    (net (code "52") (name "Net-(F1-Pad1)") (class "Default")
      (node (ref "F1") (pin "1") (pinfunction "1_1") (pintype "passive"))
      (node (ref "Q6") (pin "S") (pinfunction "S_S") (pintype "passive"))
      (node (ref "R29") (pin "1") (pinfunction "1_1") (pintype "passive"))
    )
    (net (code "53") (name "Net-(LD1-B)") (class "Default")
      (node (ref "LD1") (pin "3") (pinfunction "B_3") (pintype "passive"))
      (node (ref "R44") (pin "2") (pinfunction "2_2") (pintype "passive"))
    )
    (net (code "54") (name "Net-(LD1-G)") (class "Default")
      (node (ref "LD1") (pin "2") (pinfunction "G_2") (pintype "passive"))
      (node (ref "R43") (pin "2") (pinfunction "2_2") (pintype "passive"))
    )
    (net (code "55") (name "Net-(LD1-R)") (class "Default")
      (node (ref "LD1") (pin "1") (pinfunction "R_1") (pintype "passive"))
      (node (ref "R42") (pin "2") (pinfunction "2_2") (pintype "passive"))
    )
    (net (code "56") (name "Net-(Q1-G)") (class "Default")
      (node (ref "Q1") (pin "1") (pinfunction "G_1") (pintype "passive"))
      (node (ref "R10") (pin "2") (pinfunction "2_2") (pintype "passive"))
      (node (ref "R16") (pin "1") (pinfunction "1_1") (pintype "passive"))
    )
    (net (code "57") (name "Net-(Q2-G)") (class "Default")
      (node (ref "Q2") (pin "1") (pinfunction "G_1") (pintype "passive"))
      (node (ref "R11") (pin "2") (pinfunction "2_2") (pintype "passive"))
      (node (ref "R17") (pin "1") (pinfunction "1_1") (pintype "passive"))
    )
    (net (code "58") (name "Net-(Q3-G)") (class "Default")
      (node (ref "Q3") (pin "1") (pinfunction "G_1") (pintype "passive"))
      (node (ref "R12") (pin "2") (pinfunction "2_2") (pintype "passive"))
      (node (ref "R18") (pin "1") (pinfunction "1_1") (pintype "passive"))
    )
    (net (code "59") (name "Net-(Q4-G)") (class "Default")
      (node (ref "Q4") (pin "1") (pinfunction "G_1") (pintype "passive"))
      (node (ref "R13") (pin "2") (pinfunction "2_2") (pintype "passive"))
      (node (ref "R19") (pin "1") (pinfunction "1_1") (pintype "passive"))
    )
    (net (code "60") (name "Net-(Q5-G)") (class "Default")
      (node (ref "Q5") (pin "1") (pinfunction "G_1") (pintype "passive"))
      (node (ref "R14") (pin "2") (pinfunction "2_2") (pintype "passive"))
      (node (ref "R20") (pin "1") (pinfunction "1_1") (pintype "passive"))
    )
    (net (code "61") (name "Net-(Q7-D)") (class "Default")
      (node (ref "Q6") (pin "G") (pinfunction "G_G") (pintype "passive"))
      (node (ref "Q7") (pin "2") (pinfunction "D_2") (pintype "passive"))
      (node (ref "R29") (pin "2") (pinfunction "2_2") (pintype "passive"))
    )
    (net (code "62") (name "Net-(Q7-G)") (class "Default")
      (node (ref "Q7") (pin "1") (pinfunction "G_1") (pintype "passive"))
      (node (ref "R35") (pin "2") (pinfunction "2_2") (pintype "passive"))
      (node (ref "R38") (pin "1") (pinfunction "1_1") (pintype "passive"))
    )
    (net (code "63") (name "Net-(Q8-D)") (class "Default")
      (node (ref "Q8") (pin "2") (pinfunction "D_2") (pintype "passive"))
      (node (ref "R30") (pin "1") (pinfunction "1_1") (pintype "passive"))
      (node (ref "R32") (pin "2") (pinfunction "2_2") (pintype "passive"))
    )
    (net (code "64") (name "Net-(Q8-G)") (class "Default")
      (node (ref "Q8") (pin "1") (pinfunction "G_1") (pintype "passive"))
      (node (ref "R36") (pin "2") (pinfunction "2_2") (pintype "passive"))
      (node (ref "R39") (pin "1") (pinfunction "1_1") (pintype "passive"))
    )
    (net (code "65") (name "Net-(Q9-D)") (class "Default")
      (node (ref "Q9") (pin "2") (pinfunction "D_2") (pintype "passive"))
      (node (ref "R31") (pin "1") (pinfunction "1_1") (pintype "passive"))
      (node (ref "R33") (pin "2") (pinfunction "2_2") (pintype "passive"))
    )
    (net (code "66") (name "Net-(Q9-G)") (class "Default")
      (node (ref "Q9") (pin "1") (pinfunction "G_1") (pintype "passive"))
      (node (ref "R37") (pin "2") (pinfunction "2_2") (pintype "passive"))
      (node (ref "R40") (pin "1") (pinfunction "1_1") (pintype "passive"))
    )
    (net (code "67") (name "Net-(U2-VDD_CORE)") (class "Default")
      (node (ref "C4") (pin "1") (pinfunction "1_1") (pintype "passive"))
      (node (ref "U2") (pin "29") (pinfunction "VDD_CORE_29") (pintype "passive"))
    )
    (net (code "68") (name "Net-(U2-XIN32{slash}PA00)") (class "Default")
      (node (ref "C11") (pin "2") (pinfunction "2_2") (pintype "passive"))
      (node (ref "U2") (pin "1") (pinfunction "XIN32/PA00_1") (pintype "passive"))
      (node (ref "X1") (pin "1") (pinfunction "OSC1_1") (pintype "passive"))
    )
    (net (code "69") (name "Net-(U2-XOUT32{slash}PA01)") (class "Default")
      (node (ref "C12") (pin "1") (pinfunction "1_1") (pintype "passive"))
      (node (ref "U2") (pin "2") (pinfunction "XOUT32/PA01_2") (pintype "passive"))
      (node (ref "X1") (pin "2") (pinfunction "OSC2_2") (pintype "passive"))
    )
    (net (code "70") (name "Net-(U3-CB)") (class "Default")
      (node (ref "C9") (pin "2") (pinfunction "2_2") (pintype "passive"))
      (node (ref "U3") (pin "1") (pinfunction "CB_1") (pintype "input"))
    )
    (net (code "71") (name "Net-(U3-FB)") (class "Default")
      (node (ref "R6") (pin "1") (pinfunction "1_1") (pintype "passive"))
      (node (ref "R7") (pin "1") (pinfunction "1_1") (pintype "passive"))
      (node (ref "U3") (pin "3") (pinfunction "FB_3") (pintype "input"))
    )
    (net (code "72") (name "Net-(U5A-VINA-)") (class "Default")
      (node (ref "R15") (pin "1") (pinfunction "1_1") (pintype "passive"))
      (node (ref "R26") (pin "1") (pinfunction "1_1") (pintype "passive"))
      (node (ref "U5") (pin "2") (pinfunction "VINA-_2") (pintype "tri_state"))
    )
    (net (code "73") (name "Net-(U5A-VOUTA)") (class "Default")
      (node (ref "R26") (pin "2") (pinfunction "2_2") (pintype "passive"))
      (node (ref "R27") (pin "1") (pinfunction "1_1") (pintype "passive"))
      (node (ref "U5") (pin "1") (pinfunction "VOUTA_1") (pintype "passive"))
    )
    (net (code "74") (name "Net-(U5B-VINB+)") (class "Default")
      (node (ref "C18") (pin "1") (pinfunction "1_1") (pintype "passive"))
      (node (ref "R28") (pin "2") (pinfunction "2_2") (pintype "passive"))
      (node (ref "U5") (pin "5") (pinfunction "VINB+_5") (pintype "tri_state"))
    )
    (net (code "75") (name "Net-(U5B-VINB-)") (class "Default")
      (node (ref "R34") (pin "2") (pinfunction "2_2") (pintype "passive"))
      (node (ref "R41") (pin "1") (pinfunction "1_1") (pintype "passive"))
      (node (ref "U5") (pin "6") (pinfunction "VINB-_6") (pintype "tri_state"))
    )
    (net (code "76") (name "Net-(USB1-CC1)") (class "Default")
      (node (ref "R1") (pin "1") (pinfunction "1_1") (pintype "passive"))
      (node (ref "USB1") (pin "A5") (pinfunction "CC1_A5") (pintype "passive"))
    )
    (net (code "77") (name "Net-(USB1-CC2)") (class "Default")
      (node (ref "R3") (pin "1") (pinfunction "1_1") (pintype "passive"))
      (node (ref "USB1") (pin "B5") (pinfunction "CC2_B5") (pintype "passive"))
    )
    (net (code "78") (name "VBUS") (class "Default")
      (node (ref "D3") (pin "2") (pinfunction "A_2") (pintype "passive"))
      (node (ref "U4") (pin "2") (pinfunction "V+_2") (pintype "power_in"))
      (node (ref "USB1") (pin "A4") (pinfunction "Vbus_A4") (pintype "power_in"))
      (node (ref "USB1") (pin "A9") (pinfunction "Vbus_A9") (pintype "power_in"))
      (node (ref "USB1") (pin "B4") (pinfunction "Vbus_B4") (pintype "power_in"))
      (node (ref "USB1") (pin "B9") (pinfunction "Vbus_B9") (pintype "power_in"))
    )
    (net (code "79") (name "unconnected-(J1-NC-Pad6)") (class "Default")
      (node (ref "J1") (pin "6") (pinfunction "NC_6") (pintype "passive"))
    )
    (net (code "80") (name "unconnected-(J1-NC-Pad7)") (class "Default")
      (node (ref "J1") (pin "7") (pinfunction "NC_7") (pintype "passive"))
    )
    (net (code "81") (name "unconnected-(J1-NC-Pad8)") (class "Default")
      (node (ref "J1") (pin "8") (pinfunction "NC_8") (pintype "passive"))
    )
    (net (code "82") (name "unconnected-(J1-NC-Pad9)") (class "Default")
      (node (ref "J1") (pin "9") (pinfunction "NC_9") (pintype "passive"))
    )
    (net (code "83") (name "unconnected-(U1-NC-Pad2)") (class "Default")
      (node (ref "U1") (pin "2") (pinfunction "NC_2") (pintype "passive"))
    )
    (net (code "84") (name "unconnected-(U1-NC-Pad3)") (class "Default")
      (node (ref "U1") (pin "3") (pinfunction "NC_3") (pintype "passive"))
    )
    (net (code "85") (name "unconnected-(U1-NC-Pad5)") (class "Default")
      (node (ref "U1") (pin "5") (pinfunction "NC_5") (pintype "passive"))
    )
    (net (code "86") (name "unconnected-(U1-NC-Pad6)") (class "Default")
      (node (ref "U1") (pin "6") (pinfunction "NC_6") (pintype "passive"))
    )
    (net (code "87") (name "unconnected-(U1-NC-Pad7)") (class "Default")
      (node (ref "U1") (pin "7") (pinfunction "NC_7") (pintype "passive"))
    )
    (net (code "88") (name "unconnected-(U3-~{SHDN}-Pad4)") (class "Default")
      (node (ref "U3") (pin "4") (pinfunction "~{SHDN}_4") (pintype "input"))
    )
    (net (code "89") (name "unconnected-(U4-I{slash}O_3-Pad4)") (class "Default")
      (node (ref "U4") (pin "4") (pinfunction "I/O_3_4") (pintype "power_in"))
    )
    (net (code "90") (name "unconnected-(U4-I{slash}O_4-Pad6)") (class "Default")
      (node (ref "U4") (pin "6") (pinfunction "I/O_4_6") (pintype "power_in"))
    )
    (net (code "91") (name "unconnected-(USB1-RX1+-PadB11)") (class "Default")
      (node (ref "USB1") (pin "B11") (pinfunction "RX1+_B11") (pintype "input"))
    )
    (net (code "92") (name "unconnected-(USB1-RX1--PadB10)") (class "Default")
      (node (ref "USB1") (pin "B10") (pinfunction "RX1-_B10") (pintype "input"))
    )
    (net (code "93") (name "unconnected-(USB1-RX2+-PadA11)") (class "Default")
      (node (ref "USB1") (pin "A11") (pinfunction "RX2+_A11") (pintype "input"))
    )
    (net (code "94") (name "unconnected-(USB1-RX2--PadA10)") (class "Default")
      (node (ref "USB1") (pin "A10") (pinfunction "RX2-_A10") (pintype "input"))
    )
    (net (code "95") (name "unconnected-(USB1-SBU1-PadA8)") (class "Default")
      (node (ref "USB1") (pin "A8") (pinfunction "SBU1_A8") (pintype "passive"))
    )
    (net (code "96") (name "unconnected-(USB1-SBU2-PadB8)") (class "Default")
      (node (ref "USB1") (pin "B8") (pinfunction "SBU2_B8") (pintype "passive"))
    )
    (net (code "97") (name "unconnected-(USB1-TX1+-PadA2)") (class "Default")
      (node (ref "USB1") (pin "A2") (pinfunction "TX1+_A2") (pintype "output"))
    )
    (net (code "98") (name "unconnected-(USB1-TX1--PadA3)") (class "Default")
      (node (ref "USB1") (pin "A3") (pinfunction "TX1-_A3") (pintype "output"))
    )
    (net (code "99") (name "unconnected-(USB1-TX2+-PadB2)") (class "Default")
      (node (ref "USB1") (pin "B2") (pinfunction "TX2+_B2") (pintype "output"))
    )
    (net (code "100") (name "unconnected-(USB1-TX2--PadB3)") (class "Default")
      (node (ref "USB1") (pin "B3") (pinfunction "TX2-_B3") (pintype "output"))
    )
  )
)
